# Display70_Cape.net
KiCad netlist of a schematic drawn in EAGLE
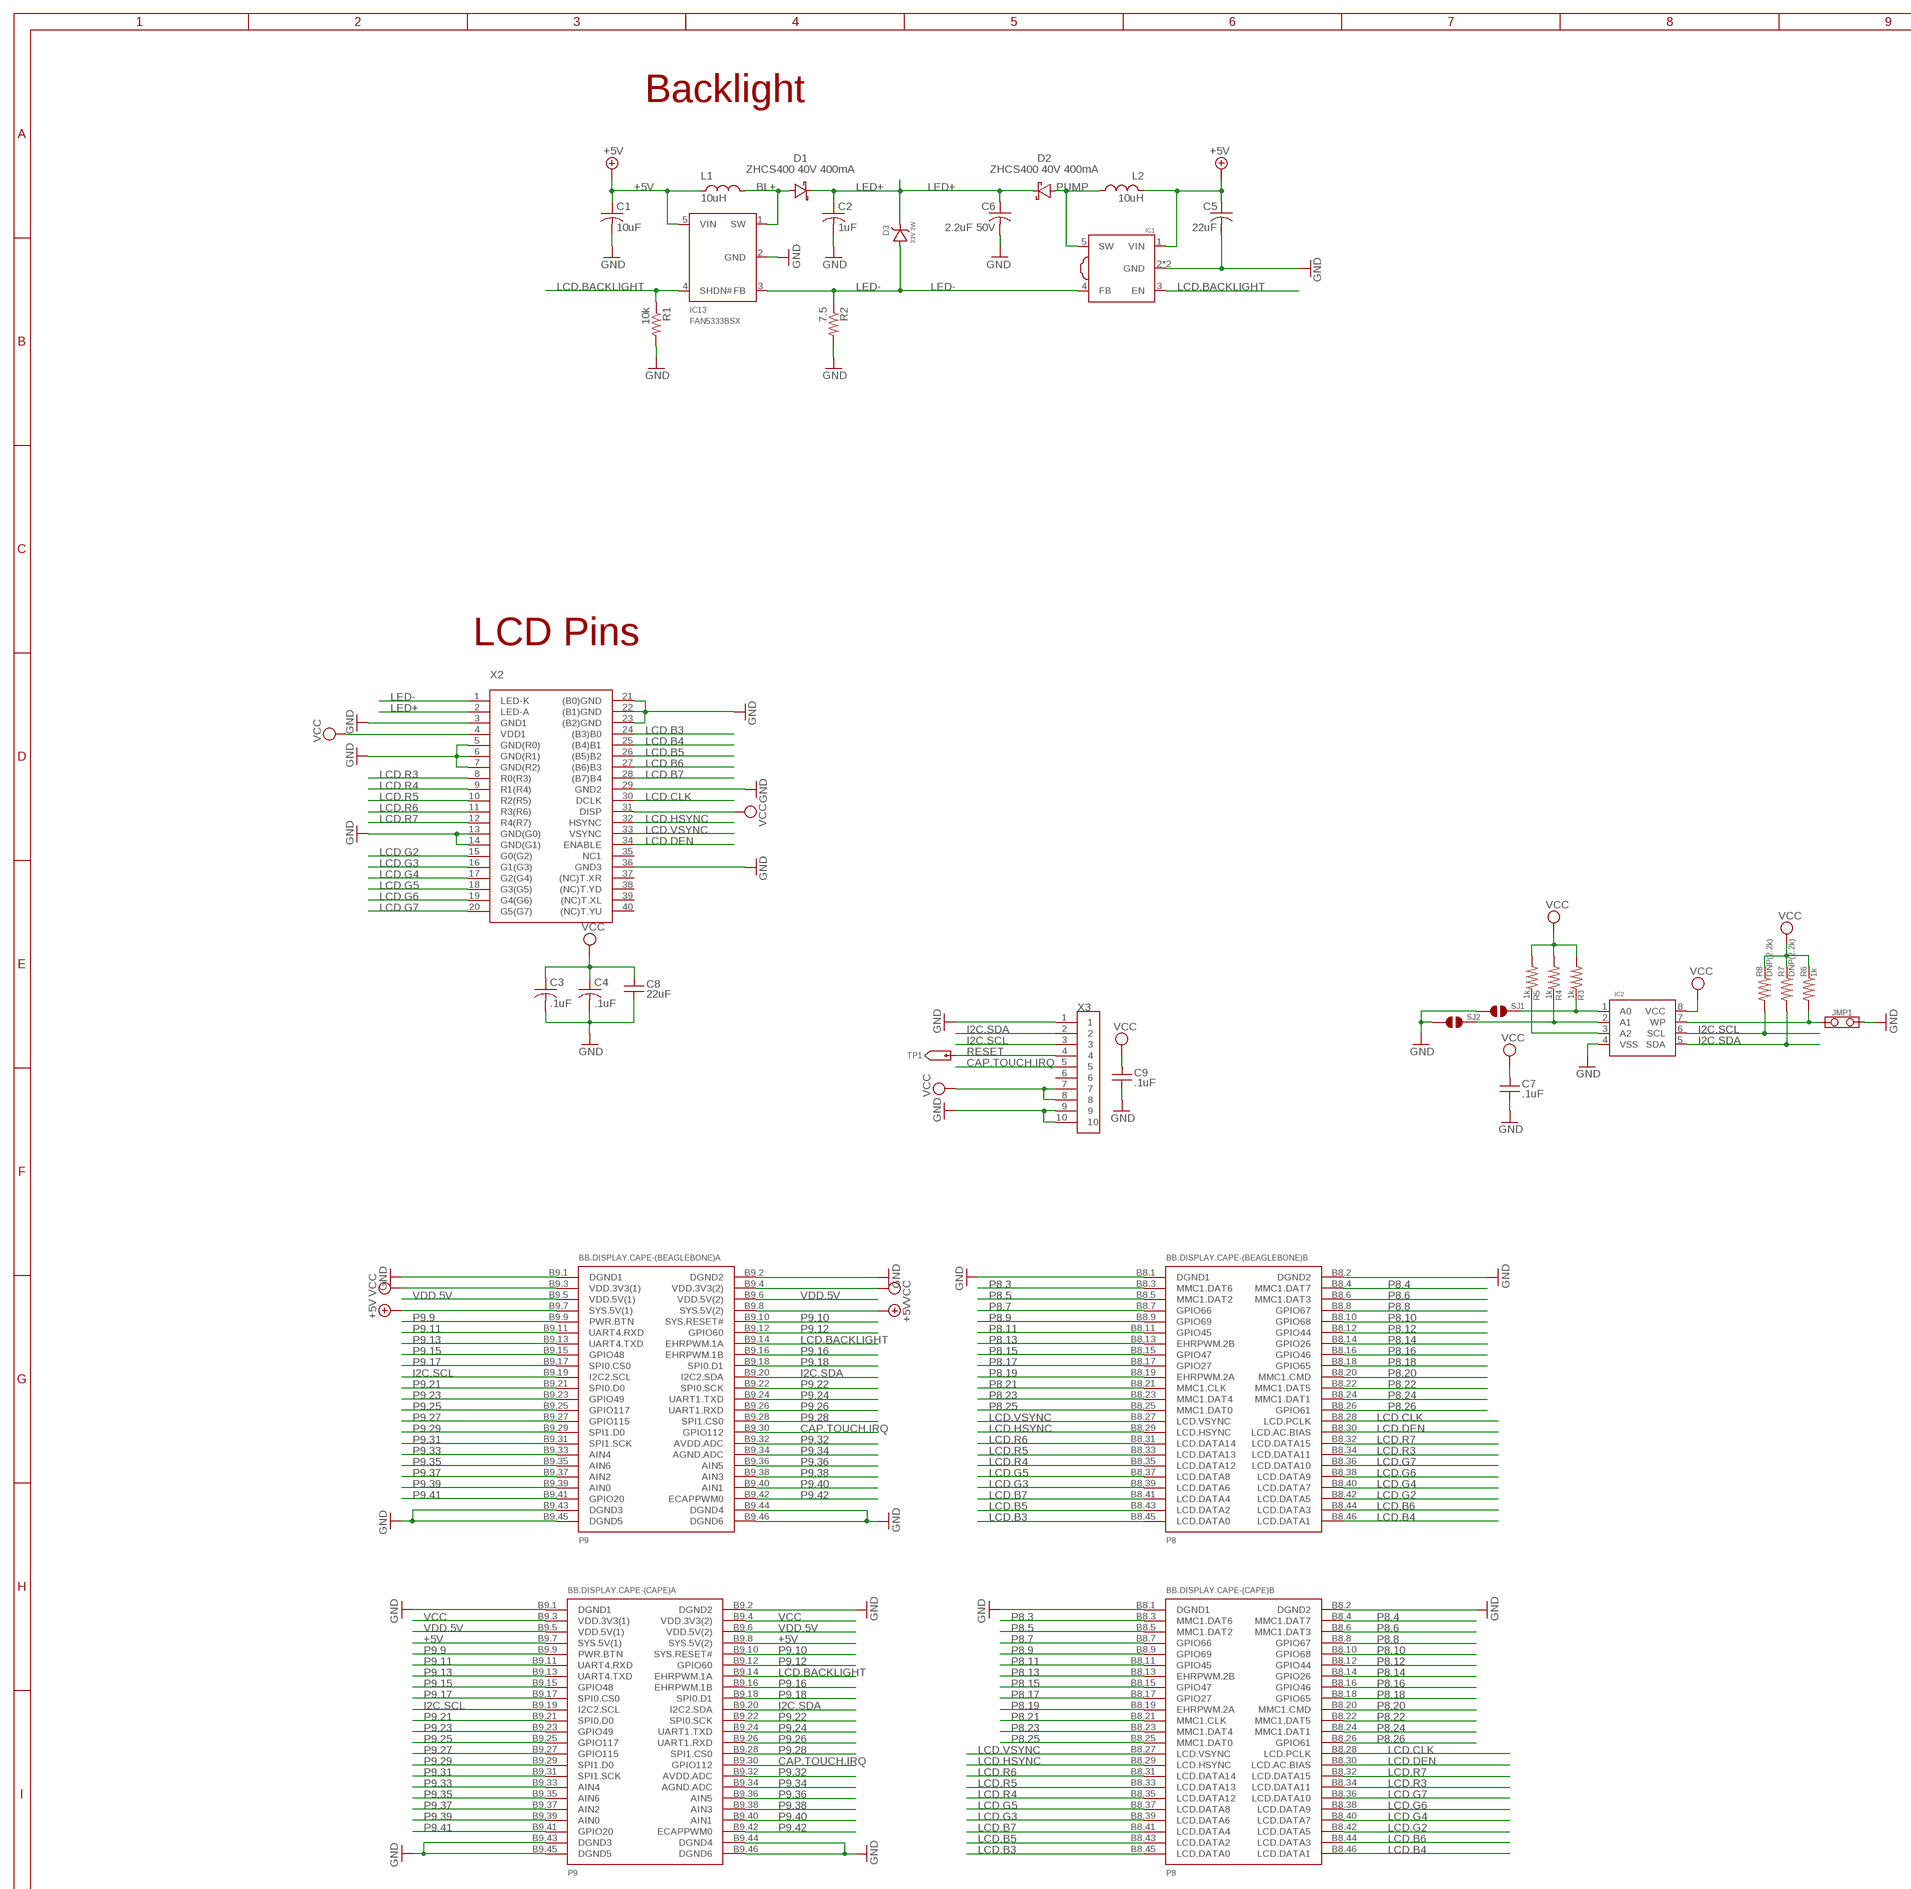
[diagram p0: schematic, sheet 1, part 1 of 2]
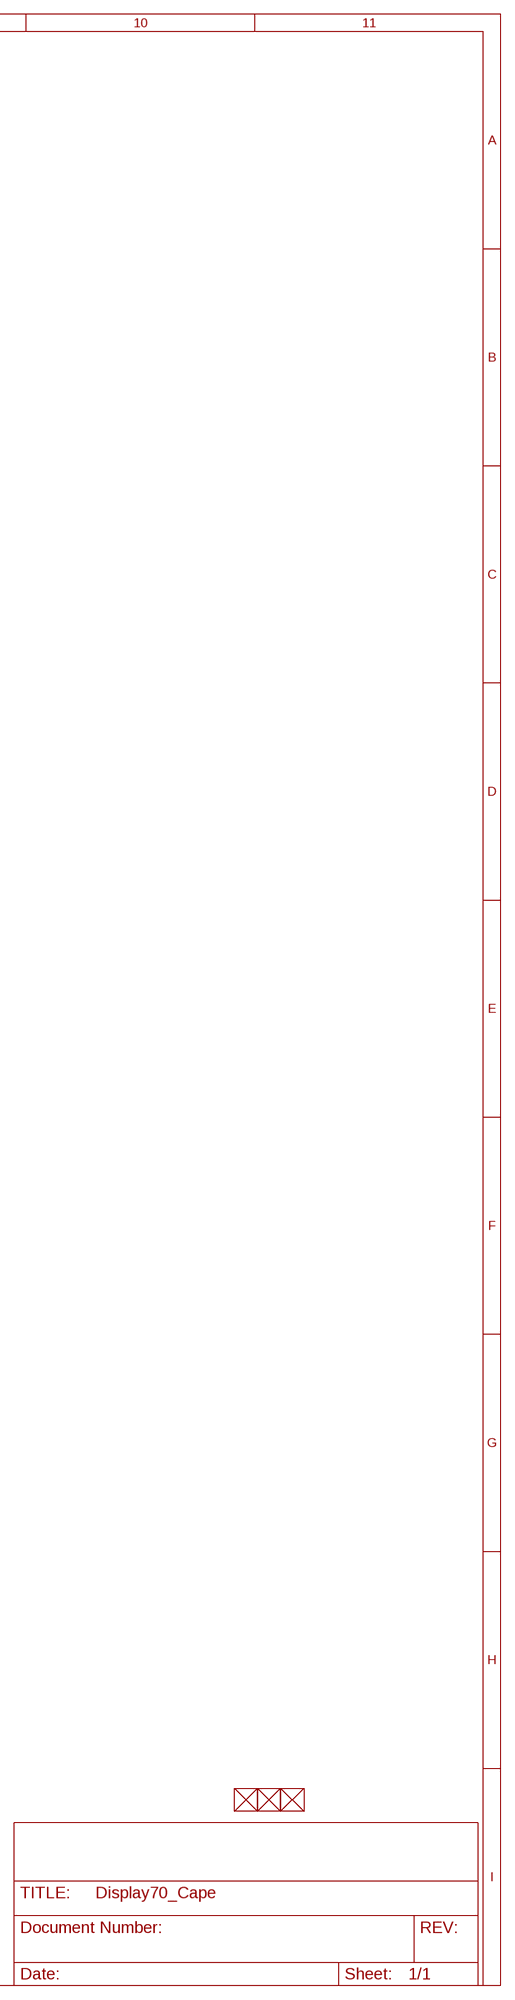
[diagram p1: schematic, sheet 1, part 2 of 2]

(export (version "E")
  (design (tool "Eeschema 10.0.6"))
  (components
    (comp (ref "BB.DISPLAY.CAPE-(BEAGLEBONE)")
      (value "BEAGLEBONE.CAPE.DISPLAY-7.BEAGLEBONE")
      (footprint "eagle-import:BEAGLEBONE.CAPE.DISPLAY-7.BEAGLEBONE")
      (libsource (lib "eagle-import") (part "BEAGLEBONE.CAPE.DISPLAY-7.BEAGLEBONE"))
    )
    (comp (ref "BB.DISPLAY.CAPE-(CAPE)")
      (value "BEAGLEBONE.CAPE.DISPLAY-7.CAPE")
      (footprint "eagle-import:BEAGLEBONE.CAPE.DISPLAY-7.CAPE")
      (libsource (lib "eagle-import") (part "BEAGLEBONE.CAPE.DISPLAY-7.CAPE"))
    )
    (comp (ref "C1")
      (value "10uF")
      (footprint "eagle-import:C0603K")
      (libsource (lib "eagle-import") (part "C-USC0603K"))
    )
    (comp (ref "C2")
      (value "1uF")
      (footprint "eagle-import:C0805K")
      (libsource (lib "eagle-import") (part "C-USC0805K"))
    )
    (comp (ref "C3")
      (value ".1uF")
      (footprint "eagle-import:C0402K")
      (libsource (lib "eagle-import") (part "C-USC0402K"))
    )
    (comp (ref "C4")
      (value ".1uF")
      (footprint "eagle-import:C0402K")
      (libsource (lib "eagle-import") (part "C-USC0402K"))
    )
    (comp (ref "C5")
      (value "22uF")
      (footprint "eagle-import:C0603K")
      (libsource (lib "eagle-import") (part "C-USC0603K"))
    )
    (comp (ref "C6")
      (value "2.2uF 50V")
      (footprint "eagle-import:C0805K")
      (libsource (lib "eagle-import") (part "C-USC0805K"))
    )
    (comp (ref "C7")
      (value ".1uF")
      (footprint "eagle-import:0402")
      (libsource (lib "eagle-import") (part "CAPACITOR-(INCH)-0402"))
    )
    (comp (ref "C8")
      (value "22uF")
      (footprint "eagle-import:0805")
      (libsource (lib "eagle-import") (part "CAPACITOR-(INCH)-0805"))
    )
    (comp (ref "C9")
      (value ".1uF")
      (footprint "eagle-import:0402")
      (libsource (lib "eagle-import") (part "CAPACITOR-(INCH)-0402"))
    )
    (comp (ref "D1")
      (value "ZHCS400 40V 400mA")
      (footprint "eagle-import:SOD323(NXP)WAVE")
      (libsource (lib "eagle-import") (part "DIODE-SCHOTTKY-(NXP)-SOD323-(WAVE)"))
    )
    (comp (ref "D2")
      (value "ZHCS400 40V 400mA")
      (footprint "eagle-import:SOD323(NXP)WAVE")
      (libsource (lib "eagle-import") (part "DIODE-SCHOTTKY-(NXP)-SOD323-(WAVE)"))
    )
    (comp (ref "D3")
      (value "33V 3W")
      (footprint "eagle-import:SMB(ON.SEMI)")
      (libsource (lib "eagle-import") (part "DIODE-ZENER-"))
    )
    (comp (ref "FUD1")
      (value "FIDUCIAL")
      (footprint "eagle-import:FIDUCIAL_40MIL")
      (libsource (lib "eagle-import") (part "FIDUCIAL"))
    )
    (comp (ref "FUD2")
      (value "FIDUCIAL")
      (footprint "eagle-import:FIDUCIAL_40MIL")
      (libsource (lib "eagle-import") (part "FIDUCIAL"))
    )
    (comp (ref "FUD3")
      (value "FIDUCIAL")
      (footprint "eagle-import:FIDUCIAL_40MIL")
      (libsource (lib "eagle-import") (part "FIDUCIAL"))
    )
    (comp (ref "IC1")
      (value "PT4110")
      (footprint "eagle-import:SOT89-5(DIODES)")
      (libsource (lib "eagle-import") (part "PT4110"))
    )
    (comp (ref "IC2")
      (value "CAT24C32")
      (footprint "eagle-import:UDFN8,2X3(ON-SEMI)")
      (libsource (lib "eagle-import") (part "CAT24C32"))
    )
    (comp (ref "IC13")
      (value "FAN5333BSX")
      (footprint "eagle-import:SOT23-5(FAIRCHILD)")
      (libsource (lib "eagle-import") (part "FAN533X"))
    )
    (comp (ref "JMP1")
      (value "JUMPER-(X2)")
      (footprint "eagle-import:JUMPER-(X2)")
      (libsource (lib "eagle-import") (part "JUMPER-(X2)"))
    )
    (comp (ref "L1")
      (value "10uH")
      (footprint "eagle-import:NRS(TAIYO.YUDEN)")
      (libsource (lib "eagle-import") (part "INDUCTOR-(TAIYO-YUDEN)-NRS5030"))
    )
    (comp (ref "L2")
      (value "10uH")
      (footprint "eagle-import:NRS(TAIYO.YUDEN)")
      (libsource (lib "eagle-import") (part "INDUCTOR-(TAIYO-YUDEN)-NRS5030"))
    )
    (comp (ref "R1")
      (value "10k")
      (footprint "eagle-import:R0603")
      (libsource (lib "eagle-import") (part "R-US_R0603"))
    )
    (comp (ref "R2")
      (value "7.5")
      (footprint "eagle-import:R0603")
      (libsource (lib "eagle-import") (part "R-US_R0603"))
    )
    (comp (ref "R3")
      (value "1k")
      (footprint "eagle-import:0402")
      (libsource (lib "eagle-import") (part "RESISTOR-(INCH)-0402"))
    )
    (comp (ref "R4")
      (value "1k")
      (footprint "eagle-import:0402")
      (libsource (lib "eagle-import") (part "RESISTOR-(INCH)-0402"))
    )
    (comp (ref "R5")
      (value "1k")
      (footprint "eagle-import:0402")
      (libsource (lib "eagle-import") (part "RESISTOR-(INCH)-0402"))
    )
    (comp (ref "R6")
      (value "1k")
      (footprint "eagle-import:0402")
      (libsource (lib "eagle-import") (part "RESISTOR-(INCH)-0402"))
    )
    (comp (ref "R7")
      (value "DNP(2.2k)")
      (footprint "eagle-import:0402")
      (libsource (lib "eagle-import") (part "RESISTOR-(INCH)-0402"))
    )
    (comp (ref "R8")
      (value "DNP(2.2k)")
      (footprint "eagle-import:0402")
      (libsource (lib "eagle-import") (part "RESISTOR-(INCH)-0402"))
    )
    (comp (ref "SJ1")
      (value "SOLDER.JOINT-(INCH)-0402")
      (footprint "eagle-import:SOLDER.JOINT(0402)")
      (libsource (lib "eagle-import") (part "SOLDER.JOINT-(INCH)-0402"))
    )
    (comp (ref "SJ2")
      (value "SOLDER.JOINT-(INCH)-0402")
      (footprint "eagle-import:SOLDER.JOINT(0402)")
      (libsource (lib "eagle-import") (part "SOLDER.JOINT-(INCH)-0402"))
    )
    (comp (ref "TP1")
      (value "TESTPAD/W_HOLE_1X1")
      (footprint "eagle-import:TESTPAD_W_HOLE_1X1")
      (libsource (lib "eagle-import") (part "TESTPAD/W_HOLE_1X1"))
    )
    (comp (ref "X2")
      (value "LCD-40PIN_FFC/FPC_0.5MM_PITCH")
      (footprint "eagle-import:KISD04-40_T1_E")
      (libsource (lib "eagle-import") (part "LCD-40PIN_FFC/FPC_0.5MM_PITCH"))
    )
    (comp (ref "X3")
      (value "10-PIN-(0.5MM-PITCH)-FPC-CONNECTOR")
      (footprint "eagle-import:10-PIN-(0.5MM-PITCH)-FPC-CONNECTOR")
      (libsource (lib "eagle-import") (part "10-PIN-(0.5MM-PITCH)-FPC-CONNECTOR"))
    )
  )
  (nets
    (net (code "1") (name "+5V") (class "Default")
      (node (ref "BB.DISPLAY.CAPE-(BEAGLEBONE)") (pin "B9.7") (pinfunction "SYS.5V(1)_B9.7") (pintype "bidirectional"))
      (node (ref "BB.DISPLAY.CAPE-(BEAGLEBONE)") (pin "B9.8") (pinfunction "SYS.5V(2)_B9.8") (pintype "bidirectional"))
      (node (ref "BB.DISPLAY.CAPE-(CAPE)") (pin "B9.7") (pinfunction "SYS.5V(1)_B9.7") (pintype "bidirectional"))
      (node (ref "BB.DISPLAY.CAPE-(CAPE)") (pin "B9.8") (pinfunction "SYS.5V(2)_B9.8") (pintype "bidirectional"))
      (node (ref "C1") (pin "1") (pinfunction "1_1") (pintype "passive"))
      (node (ref "C5") (pin "1") (pinfunction "1_1") (pintype "passive"))
      (node (ref "IC1") (pin "1") (pinfunction "VIN_1") (pintype "bidirectional"))
      (node (ref "IC13") (pin "5") (pinfunction "VIN_5") (pintype "bidirectional"))
      (node (ref "L1") (pin "1") (pinfunction "1_1") (pintype "bidirectional"))
      (node (ref "L2") (pin "1") (pinfunction "1_1") (pintype "bidirectional"))
    )
    (net (code "2") (name "/BL+") (class "Default")
      (node (ref "D1") (pin "A") (pinfunction "ANODE_A") (pintype "bidirectional"))
      (node (ref "IC13") (pin "1") (pinfunction "SW_1") (pintype "bidirectional"))
      (node (ref "L1") (pin "2") (pinfunction "2_2") (pintype "bidirectional"))
    )
    (net (code "3") (name "/CAP.TOUCH.IRQ") (class "Default")
      (node (ref "BB.DISPLAY.CAPE-(BEAGLEBONE)") (pin "B9.30") (pinfunction "GPIO112_B9.30") (pintype "bidirectional"))
      (node (ref "BB.DISPLAY.CAPE-(CAPE)") (pin "B9.30") (pinfunction "GPIO112_B9.30") (pintype "bidirectional"))
      (node (ref "X3") (pin "5") (pinfunction "5_5") (pintype "bidirectional"))
    )
    (net (code "4") (name "/I2C.SCL") (class "Default")
      (node (ref "BB.DISPLAY.CAPE-(BEAGLEBONE)") (pin "B9.19") (pinfunction "I2C2.SCL_B9.19") (pintype "bidirectional"))
      (node (ref "BB.DISPLAY.CAPE-(CAPE)") (pin "B9.19") (pinfunction "I2C2.SCL_B9.19") (pintype "bidirectional"))
      (node (ref "IC2") (pin "6") (pinfunction "SCL_6") (pintype "bidirectional"))
      (node (ref "R8") (pin "1") (pinfunction "1_1") (pintype "bidirectional"))
      (node (ref "X3") (pin "3") (pinfunction "3_3") (pintype "bidirectional"))
    )
    (net (code "5") (name "/I2C.SDA") (class "Default")
      (node (ref "BB.DISPLAY.CAPE-(BEAGLEBONE)") (pin "B9.20") (pinfunction "I2C2.SDA_B9.20") (pintype "bidirectional"))
      (node (ref "BB.DISPLAY.CAPE-(CAPE)") (pin "B9.20") (pinfunction "I2C2.SDA_B9.20") (pintype "bidirectional"))
      (node (ref "IC2") (pin "5") (pinfunction "SDA_5") (pintype "bidirectional"))
      (node (ref "R7") (pin "1") (pinfunction "1_1") (pintype "bidirectional"))
      (node (ref "X3") (pin "2") (pinfunction "2_2") (pintype "bidirectional"))
    )
    (net (code "6") (name "/LCD.B3") (class "Default")
      (node (ref "BB.DISPLAY.CAPE-(BEAGLEBONE)") (pin "B8.45") (pinfunction "LCD.DATA0_B8.45") (pintype "bidirectional"))
      (node (ref "BB.DISPLAY.CAPE-(CAPE)") (pin "B8.45") (pinfunction "LCD.DATA0_B8.45") (pintype "bidirectional"))
      (node (ref "X2") (pin "24") (pinfunction "(B3)B0_24") (pintype "bidirectional"))
    )
    (net (code "7") (name "/LCD.B4") (class "Default")
      (node (ref "BB.DISPLAY.CAPE-(BEAGLEBONE)") (pin "B8.46") (pinfunction "LCD.DATA1_B8.46") (pintype "bidirectional"))
      (node (ref "BB.DISPLAY.CAPE-(CAPE)") (pin "B8.46") (pinfunction "LCD.DATA1_B8.46") (pintype "bidirectional"))
      (node (ref "X2") (pin "25") (pinfunction "(B4)B1_25") (pintype "bidirectional"))
    )
    (net (code "8") (name "/LCD.B5") (class "Default")
      (node (ref "BB.DISPLAY.CAPE-(BEAGLEBONE)") (pin "B8.43") (pinfunction "LCD.DATA2_B8.43") (pintype "bidirectional"))
      (node (ref "BB.DISPLAY.CAPE-(CAPE)") (pin "B8.43") (pinfunction "LCD.DATA2_B8.43") (pintype "bidirectional"))
      (node (ref "X2") (pin "26") (pinfunction "(B5)B2_26") (pintype "bidirectional"))
    )
    (net (code "9") (name "/LCD.B6") (class "Default")
      (node (ref "BB.DISPLAY.CAPE-(BEAGLEBONE)") (pin "B8.44") (pinfunction "LCD.DATA3_B8.44") (pintype "bidirectional"))
      (node (ref "BB.DISPLAY.CAPE-(CAPE)") (pin "B8.44") (pinfunction "LCD.DATA3_B8.44") (pintype "bidirectional"))
      (node (ref "X2") (pin "27") (pinfunction "(B6)B3_27") (pintype "bidirectional"))
    )
    (net (code "10") (name "/LCD.B7") (class "Default")
      (node (ref "BB.DISPLAY.CAPE-(BEAGLEBONE)") (pin "B8.41") (pinfunction "LCD.DATA4_B8.41") (pintype "bidirectional"))
      (node (ref "BB.DISPLAY.CAPE-(CAPE)") (pin "B8.41") (pinfunction "LCD.DATA4_B8.41") (pintype "bidirectional"))
      (node (ref "X2") (pin "28") (pinfunction "(B7)B4_28") (pintype "bidirectional"))
    )
    (net (code "11") (name "/LCD.BACKLIGHT") (class "Default")
      (node (ref "BB.DISPLAY.CAPE-(BEAGLEBONE)") (pin "B9.14") (pinfunction "EHRPWM.1A_B9.14") (pintype "bidirectional"))
      (node (ref "BB.DISPLAY.CAPE-(CAPE)") (pin "B9.14") (pinfunction "EHRPWM.1A_B9.14") (pintype "bidirectional"))
      (node (ref "IC1") (pin "3") (pinfunction "EN_3") (pintype "bidirectional"))
      (node (ref "IC13") (pin "4") (pinfunction "SHDN#_4") (pintype "bidirectional"))
      (node (ref "R1") (pin "1") (pinfunction "1_1") (pintype "passive"))
    )
    (net (code "12") (name "/LCD.CLK") (class "Default")
      (node (ref "BB.DISPLAY.CAPE-(BEAGLEBONE)") (pin "B8.28") (pinfunction "LCD.PCLK_B8.28") (pintype "bidirectional"))
      (node (ref "BB.DISPLAY.CAPE-(CAPE)") (pin "B8.28") (pinfunction "LCD.PCLK_B8.28") (pintype "bidirectional"))
      (node (ref "X2") (pin "30") (pinfunction "DCLK_30") (pintype "bidirectional"))
    )
    (net (code "13") (name "/LCD.DEN") (class "Default")
      (node (ref "BB.DISPLAY.CAPE-(BEAGLEBONE)") (pin "B8.30") (pinfunction "LCD.AC.BIAS_B8.30") (pintype "bidirectional"))
      (node (ref "BB.DISPLAY.CAPE-(CAPE)") (pin "B8.30") (pinfunction "LCD.AC.BIAS_B8.30") (pintype "bidirectional"))
      (node (ref "X2") (pin "34") (pinfunction "ENABLE_34") (pintype "bidirectional"))
    )
    (net (code "14") (name "/LCD.G2") (class "Default")
      (node (ref "BB.DISPLAY.CAPE-(BEAGLEBONE)") (pin "B8.42") (pinfunction "LCD.DATA5_B8.42") (pintype "bidirectional"))
      (node (ref "BB.DISPLAY.CAPE-(CAPE)") (pin "B8.42") (pinfunction "LCD.DATA5_B8.42") (pintype "bidirectional"))
      (node (ref "X2") (pin "15") (pinfunction "G0(G2)_15") (pintype "bidirectional"))
    )
    (net (code "15") (name "/LCD.G3") (class "Default")
      (node (ref "BB.DISPLAY.CAPE-(BEAGLEBONE)") (pin "B8.39") (pinfunction "LCD.DATA6_B8.39") (pintype "bidirectional"))
      (node (ref "BB.DISPLAY.CAPE-(CAPE)") (pin "B8.39") (pinfunction "LCD.DATA6_B8.39") (pintype "bidirectional"))
      (node (ref "X2") (pin "16") (pinfunction "G1(G3)_16") (pintype "bidirectional"))
    )
    (net (code "16") (name "/LCD.G4") (class "Default")
      (node (ref "BB.DISPLAY.CAPE-(BEAGLEBONE)") (pin "B8.40") (pinfunction "LCD.DATA7_B8.40") (pintype "bidirectional"))
      (node (ref "BB.DISPLAY.CAPE-(CAPE)") (pin "B8.40") (pinfunction "LCD.DATA7_B8.40") (pintype "bidirectional"))
      (node (ref "X2") (pin "17") (pinfunction "G2(G4)_17") (pintype "bidirectional"))
    )
    (net (code "17") (name "/LCD.G5") (class "Default")
      (node (ref "BB.DISPLAY.CAPE-(BEAGLEBONE)") (pin "B8.37") (pinfunction "LCD.DATA8_B8.37") (pintype "bidirectional"))
      (node (ref "BB.DISPLAY.CAPE-(CAPE)") (pin "B8.37") (pinfunction "LCD.DATA8_B8.37") (pintype "bidirectional"))
      (node (ref "X2") (pin "18") (pinfunction "G3(G5)_18") (pintype "bidirectional"))
    )
    (net (code "18") (name "/LCD.G6") (class "Default")
      (node (ref "BB.DISPLAY.CAPE-(BEAGLEBONE)") (pin "B8.38") (pinfunction "LCD.DATA9_B8.38") (pintype "bidirectional"))
      (node (ref "BB.DISPLAY.CAPE-(CAPE)") (pin "B8.38") (pinfunction "LCD.DATA9_B8.38") (pintype "bidirectional"))
      (node (ref "X2") (pin "19") (pinfunction "G4(G6)_19") (pintype "bidirectional"))
    )
    (net (code "19") (name "/LCD.G7") (class "Default")
      (node (ref "BB.DISPLAY.CAPE-(BEAGLEBONE)") (pin "B8.36") (pinfunction "LCD.DATA10_B8.36") (pintype "bidirectional"))
      (node (ref "BB.DISPLAY.CAPE-(CAPE)") (pin "B8.36") (pinfunction "LCD.DATA10_B8.36") (pintype "bidirectional"))
      (node (ref "X2") (pin "20") (pinfunction "G5(G7)_20") (pintype "bidirectional"))
    )
    (net (code "20") (name "/LCD.HSYNC") (class "Default")
      (node (ref "BB.DISPLAY.CAPE-(BEAGLEBONE)") (pin "B8.29") (pinfunction "LCD.HSYNC_B8.29") (pintype "bidirectional"))
      (node (ref "BB.DISPLAY.CAPE-(CAPE)") (pin "B8.29") (pinfunction "LCD.HSYNC_B8.29") (pintype "bidirectional"))
      (node (ref "X2") (pin "32") (pinfunction "HSYNC_32") (pintype "bidirectional"))
    )
    (net (code "21") (name "/LCD.R3") (class "Default")
      (node (ref "BB.DISPLAY.CAPE-(BEAGLEBONE)") (pin "B8.34") (pinfunction "LCD.DATA11_B8.34") (pintype "bidirectional"))
      (node (ref "BB.DISPLAY.CAPE-(CAPE)") (pin "B8.34") (pinfunction "LCD.DATA11_B8.34") (pintype "bidirectional"))
      (node (ref "X2") (pin "8") (pinfunction "R0(R3)_8") (pintype "bidirectional"))
    )
    (net (code "22") (name "/LCD.R4") (class "Default")
      (node (ref "BB.DISPLAY.CAPE-(BEAGLEBONE)") (pin "B8.35") (pinfunction "LCD.DATA12_B8.35") (pintype "bidirectional"))
      (node (ref "BB.DISPLAY.CAPE-(CAPE)") (pin "B8.35") (pinfunction "LCD.DATA12_B8.35") (pintype "bidirectional"))
      (node (ref "X2") (pin "9") (pinfunction "R1(R4)_9") (pintype "bidirectional"))
    )
    (net (code "23") (name "/LCD.R5") (class "Default")
      (node (ref "BB.DISPLAY.CAPE-(BEAGLEBONE)") (pin "B8.33") (pinfunction "LCD.DATA13_B8.33") (pintype "bidirectional"))
      (node (ref "BB.DISPLAY.CAPE-(CAPE)") (pin "B8.33") (pinfunction "LCD.DATA13_B8.33") (pintype "bidirectional"))
      (node (ref "X2") (pin "10") (pinfunction "R2(R5)_10") (pintype "bidirectional"))
    )
    (net (code "24") (name "/LCD.R6") (class "Default")
      (node (ref "BB.DISPLAY.CAPE-(BEAGLEBONE)") (pin "B8.31") (pinfunction "LCD.DATA14_B8.31") (pintype "bidirectional"))
      (node (ref "BB.DISPLAY.CAPE-(CAPE)") (pin "B8.31") (pinfunction "LCD.DATA14_B8.31") (pintype "bidirectional"))
      (node (ref "X2") (pin "11") (pinfunction "R3(R6)_11") (pintype "bidirectional"))
    )
    (net (code "25") (name "/LCD.R7") (class "Default")
      (node (ref "BB.DISPLAY.CAPE-(BEAGLEBONE)") (pin "B8.32") (pinfunction "LCD.DATA15_B8.32") (pintype "bidirectional"))
      (node (ref "BB.DISPLAY.CAPE-(CAPE)") (pin "B8.32") (pinfunction "LCD.DATA15_B8.32") (pintype "bidirectional"))
      (node (ref "X2") (pin "12") (pinfunction "R4(R7)_12") (pintype "bidirectional"))
    )
    (net (code "26") (name "/LCD.VSYNC") (class "Default")
      (node (ref "BB.DISPLAY.CAPE-(BEAGLEBONE)") (pin "B8.27") (pinfunction "LCD.VSYNC_B8.27") (pintype "bidirectional"))
      (node (ref "BB.DISPLAY.CAPE-(CAPE)") (pin "B8.27") (pinfunction "LCD.VSYNC_B8.27") (pintype "bidirectional"))
      (node (ref "X2") (pin "33") (pinfunction "VSYNC_33") (pintype "bidirectional"))
    )
    (net (code "27") (name "/LED+") (class "Default")
      (node (ref "C2") (pin "1") (pinfunction "1_1") (pintype "passive"))
      (node (ref "C6") (pin "1") (pinfunction "1_1") (pintype "passive"))
      (node (ref "D1") (pin "C") (pinfunction "CATHODE_C") (pintype "bidirectional"))
      (node (ref "D2") (pin "C") (pinfunction "CATHODE_C") (pintype "bidirectional"))
      (node (ref "D3") (pin "K") (pinfunction "K_K") (pintype "bidirectional"))
      (node (ref "X2") (pin "2") (pinfunction "LED-A_2") (pintype "bidirectional"))
    )
    (net (code "28") (name "/LED-") (class "Default")
      (node (ref "D3") (pin "A") (pinfunction "A_A") (pintype "bidirectional"))
      (node (ref "IC1") (pin "4") (pinfunction "FB_4") (pintype "bidirectional"))
      (node (ref "IC13") (pin "3") (pinfunction "FB_3") (pintype "bidirectional"))
      (node (ref "R2") (pin "1") (pinfunction "1_1") (pintype "passive"))
      (node (ref "X2") (pin "1") (pinfunction "LED-K_1") (pintype "bidirectional"))
    )
    (net (code "29") (name "/P8.3") (class "Default")
      (node (ref "BB.DISPLAY.CAPE-(BEAGLEBONE)") (pin "B8.3") (pinfunction "MMC1.DAT6_B8.3") (pintype "bidirectional"))
      (node (ref "BB.DISPLAY.CAPE-(CAPE)") (pin "B8.3") (pinfunction "MMC1.DAT6_B8.3") (pintype "bidirectional"))
    )
    (net (code "30") (name "/P8.4") (class "Default")
      (node (ref "BB.DISPLAY.CAPE-(BEAGLEBONE)") (pin "B8.4") (pinfunction "MMC1.DAT7_B8.4") (pintype "bidirectional"))
      (node (ref "BB.DISPLAY.CAPE-(CAPE)") (pin "B8.4") (pinfunction "MMC1.DAT7_B8.4") (pintype "bidirectional"))
    )
    (net (code "31") (name "/P8.5") (class "Default")
      (node (ref "BB.DISPLAY.CAPE-(BEAGLEBONE)") (pin "B8.5") (pinfunction "MMC1.DAT2_B8.5") (pintype "bidirectional"))
      (node (ref "BB.DISPLAY.CAPE-(CAPE)") (pin "B8.5") (pinfunction "MMC1.DAT2_B8.5") (pintype "bidirectional"))
    )
    (net (code "32") (name "/P8.6") (class "Default")
      (node (ref "BB.DISPLAY.CAPE-(BEAGLEBONE)") (pin "B8.6") (pinfunction "MMC1.DAT3_B8.6") (pintype "bidirectional"))
      (node (ref "BB.DISPLAY.CAPE-(CAPE)") (pin "B8.6") (pinfunction "MMC1.DAT3_B8.6") (pintype "bidirectional"))
    )
    (net (code "33") (name "/P8.7") (class "Default")
      (node (ref "BB.DISPLAY.CAPE-(BEAGLEBONE)") (pin "B8.7") (pinfunction "GPIO66_B8.7") (pintype "bidirectional"))
      (node (ref "BB.DISPLAY.CAPE-(CAPE)") (pin "B8.7") (pinfunction "GPIO66_B8.7") (pintype "bidirectional"))
    )
    (net (code "34") (name "/P8.8") (class "Default")
      (node (ref "BB.DISPLAY.CAPE-(BEAGLEBONE)") (pin "B8.8") (pinfunction "GPIO67_B8.8") (pintype "bidirectional"))
      (node (ref "BB.DISPLAY.CAPE-(CAPE)") (pin "B8.8") (pinfunction "GPIO67_B8.8") (pintype "bidirectional"))
    )
    (net (code "35") (name "/P8.9") (class "Default")
      (node (ref "BB.DISPLAY.CAPE-(BEAGLEBONE)") (pin "B8.9") (pinfunction "GPIO69_B8.9") (pintype "bidirectional"))
      (node (ref "BB.DISPLAY.CAPE-(CAPE)") (pin "B8.9") (pinfunction "GPIO69_B8.9") (pintype "bidirectional"))
    )
    (net (code "36") (name "/P8.10") (class "Default")
      (node (ref "BB.DISPLAY.CAPE-(BEAGLEBONE)") (pin "B8.10") (pinfunction "GPIO68_B8.10") (pintype "bidirectional"))
      (node (ref "BB.DISPLAY.CAPE-(CAPE)") (pin "B8.10") (pinfunction "GPIO68_B8.10") (pintype "bidirectional"))
    )
    (net (code "37") (name "/P8.11") (class "Default")
      (node (ref "BB.DISPLAY.CAPE-(BEAGLEBONE)") (pin "B8.11") (pinfunction "GPIO45_B8.11") (pintype "bidirectional"))
      (node (ref "BB.DISPLAY.CAPE-(CAPE)") (pin "B8.11") (pinfunction "GPIO45_B8.11") (pintype "bidirectional"))
    )
    (net (code "38") (name "/P8.12") (class "Default")
      (node (ref "BB.DISPLAY.CAPE-(BEAGLEBONE)") (pin "B8.12") (pinfunction "GPIO44_B8.12") (pintype "bidirectional"))
      (node (ref "BB.DISPLAY.CAPE-(CAPE)") (pin "B8.12") (pinfunction "GPIO44_B8.12") (pintype "bidirectional"))
    )
    (net (code "39") (name "/P8.13") (class "Default")
      (node (ref "BB.DISPLAY.CAPE-(BEAGLEBONE)") (pin "B8.13") (pinfunction "EHRPWM.2B_B8.13") (pintype "bidirectional"))
      (node (ref "BB.DISPLAY.CAPE-(CAPE)") (pin "B8.13") (pinfunction "EHRPWM.2B_B8.13") (pintype "bidirectional"))
    )
    (net (code "40") (name "/P8.14") (class "Default")
      (node (ref "BB.DISPLAY.CAPE-(BEAGLEBONE)") (pin "B8.14") (pinfunction "GPIO26_B8.14") (pintype "bidirectional"))
      (node (ref "BB.DISPLAY.CAPE-(CAPE)") (pin "B8.14") (pinfunction "GPIO26_B8.14") (pintype "bidirectional"))
    )
    (net (code "41") (name "/P8.15") (class "Default")
      (node (ref "BB.DISPLAY.CAPE-(BEAGLEBONE)") (pin "B8.15") (pinfunction "GPIO47_B8.15") (pintype "bidirectional"))
      (node (ref "BB.DISPLAY.CAPE-(CAPE)") (pin "B8.15") (pinfunction "GPIO47_B8.15") (pintype "bidirectional"))
    )
    (net (code "42") (name "/P8.16") (class "Default")
      (node (ref "BB.DISPLAY.CAPE-(BEAGLEBONE)") (pin "B8.16") (pinfunction "GPIO46_B8.16") (pintype "bidirectional"))
      (node (ref "BB.DISPLAY.CAPE-(CAPE)") (pin "B8.16") (pinfunction "GPIO46_B8.16") (pintype "bidirectional"))
    )
    (net (code "43") (name "/P8.17") (class "Default")
      (node (ref "BB.DISPLAY.CAPE-(BEAGLEBONE)") (pin "B8.17") (pinfunction "GPIO27_B8.17") (pintype "bidirectional"))
      (node (ref "BB.DISPLAY.CAPE-(CAPE)") (pin "B8.17") (pinfunction "GPIO27_B8.17") (pintype "bidirectional"))
    )
    (net (code "44") (name "/P8.18") (class "Default")
      (node (ref "BB.DISPLAY.CAPE-(BEAGLEBONE)") (pin "B8.18") (pinfunction "GPIO65_B8.18") (pintype "bidirectional"))
      (node (ref "BB.DISPLAY.CAPE-(CAPE)") (pin "B8.18") (pinfunction "GPIO65_B8.18") (pintype "bidirectional"))
    )
    (net (code "45") (name "/P8.19") (class "Default")
      (node (ref "BB.DISPLAY.CAPE-(BEAGLEBONE)") (pin "B8.19") (pinfunction "EHRPWM.2A_B8.19") (pintype "bidirectional"))
      (node (ref "BB.DISPLAY.CAPE-(CAPE)") (pin "B8.19") (pinfunction "EHRPWM.2A_B8.19") (pintype "bidirectional"))
    )
    (net (code "46") (name "/P8.20") (class "Default")
      (node (ref "BB.DISPLAY.CAPE-(BEAGLEBONE)") (pin "B8.20") (pinfunction "MMC1.CMD_B8.20") (pintype "bidirectional"))
      (node (ref "BB.DISPLAY.CAPE-(CAPE)") (pin "B8.20") (pinfunction "MMC1.CMD_B8.20") (pintype "bidirectional"))
    )
    (net (code "47") (name "/P8.21") (class "Default")
      (node (ref "BB.DISPLAY.CAPE-(BEAGLEBONE)") (pin "B8.21") (pinfunction "MMC1.CLK_B8.21") (pintype "bidirectional"))
      (node (ref "BB.DISPLAY.CAPE-(CAPE)") (pin "B8.21") (pinfunction "MMC1.CLK_B8.21") (pintype "bidirectional"))
    )
    (net (code "48") (name "/P8.22") (class "Default")
      (node (ref "BB.DISPLAY.CAPE-(BEAGLEBONE)") (pin "B8.22") (pinfunction "MMC1.DAT5_B8.22") (pintype "bidirectional"))
      (node (ref "BB.DISPLAY.CAPE-(CAPE)") (pin "B8.22") (pinfunction "MMC1.DAT5_B8.22") (pintype "bidirectional"))
    )
    (net (code "49") (name "/P8.23") (class "Default")
      (node (ref "BB.DISPLAY.CAPE-(BEAGLEBONE)") (pin "B8.23") (pinfunction "MMC1.DAT4_B8.23") (pintype "bidirectional"))
      (node (ref "BB.DISPLAY.CAPE-(CAPE)") (pin "B8.23") (pinfunction "MMC1.DAT4_B8.23") (pintype "bidirectional"))
    )
    (net (code "50") (name "/P8.24") (class "Default")
      (node (ref "BB.DISPLAY.CAPE-(BEAGLEBONE)") (pin "B8.24") (pinfunction "MMC1.DAT1_B8.24") (pintype "bidirectional"))
      (node (ref "BB.DISPLAY.CAPE-(CAPE)") (pin "B8.24") (pinfunction "MMC1.DAT1_B8.24") (pintype "bidirectional"))
    )
    (net (code "51") (name "/P8.25") (class "Default")
      (node (ref "BB.DISPLAY.CAPE-(BEAGLEBONE)") (pin "B8.25") (pinfunction "MMC1.DAT0_B8.25") (pintype "bidirectional"))
      (node (ref "BB.DISPLAY.CAPE-(CAPE)") (pin "B8.25") (pinfunction "MMC1.DAT0_B8.25") (pintype "bidirectional"))
    )
    (net (code "52") (name "/P8.26") (class "Default")
      (node (ref "BB.DISPLAY.CAPE-(BEAGLEBONE)") (pin "B8.26") (pinfunction "GPIO61_B8.26") (pintype "bidirectional"))
      (node (ref "BB.DISPLAY.CAPE-(CAPE)") (pin "B8.26") (pinfunction "GPIO61_B8.26") (pintype "bidirectional"))
    )
    (net (code "53") (name "/P9.9") (class "Default")
      (node (ref "BB.DISPLAY.CAPE-(BEAGLEBONE)") (pin "B9.9") (pinfunction "PWR.BTN_B9.9") (pintype "bidirectional"))
      (node (ref "BB.DISPLAY.CAPE-(CAPE)") (pin "B9.9") (pinfunction "PWR.BTN_B9.9") (pintype "bidirectional"))
    )
    (net (code "54") (name "/P9.10") (class "Default")
      (node (ref "BB.DISPLAY.CAPE-(BEAGLEBONE)") (pin "B9.10") (pinfunction "SYS.RESET#_B9.10") (pintype "bidirectional"))
      (node (ref "BB.DISPLAY.CAPE-(CAPE)") (pin "B9.10") (pinfunction "SYS.RESET#_B9.10") (pintype "bidirectional"))
    )
    (net (code "55") (name "/P9.11") (class "Default")
      (node (ref "BB.DISPLAY.CAPE-(BEAGLEBONE)") (pin "B9.11") (pinfunction "UART4.RXD_B9.11") (pintype "bidirectional"))
      (node (ref "BB.DISPLAY.CAPE-(CAPE)") (pin "B9.11") (pinfunction "UART4.RXD_B9.11") (pintype "bidirectional"))
    )
    (net (code "56") (name "/P9.12") (class "Default")
      (node (ref "BB.DISPLAY.CAPE-(BEAGLEBONE)") (pin "B9.12") (pinfunction "GPIO60_B9.12") (pintype "bidirectional"))
      (node (ref "BB.DISPLAY.CAPE-(CAPE)") (pin "B9.12") (pinfunction "GPIO60_B9.12") (pintype "bidirectional"))
    )
    (net (code "57") (name "/P9.13") (class "Default")
      (node (ref "BB.DISPLAY.CAPE-(BEAGLEBONE)") (pin "B9.13") (pinfunction "UART4.TXD_B9.13") (pintype "bidirectional"))
      (node (ref "BB.DISPLAY.CAPE-(CAPE)") (pin "B9.13") (pinfunction "UART4.TXD_B9.13") (pintype "bidirectional"))
    )
    (net (code "58") (name "/P9.15") (class "Default")
      (node (ref "BB.DISPLAY.CAPE-(BEAGLEBONE)") (pin "B9.15") (pinfunction "GPIO48_B9.15") (pintype "bidirectional"))
      (node (ref "BB.DISPLAY.CAPE-(CAPE)") (pin "B9.15") (pinfunction "GPIO48_B9.15") (pintype "bidirectional"))
    )
    (net (code "59") (name "/P9.16") (class "Default")
      (node (ref "BB.DISPLAY.CAPE-(BEAGLEBONE)") (pin "B9.16") (pinfunction "EHRPWM.1B_B9.16") (pintype "bidirectional"))
      (node (ref "BB.DISPLAY.CAPE-(CAPE)") (pin "B9.16") (pinfunction "EHRPWM.1B_B9.16") (pintype "bidirectional"))
    )
    (net (code "60") (name "/P9.17") (class "Default")
      (node (ref "BB.DISPLAY.CAPE-(BEAGLEBONE)") (pin "B9.17") (pinfunction "SPI0.CS0_B9.17") (pintype "bidirectional"))
      (node (ref "BB.DISPLAY.CAPE-(CAPE)") (pin "B9.17") (pinfunction "SPI0.CS0_B9.17") (pintype "bidirectional"))
    )
    (net (code "61") (name "/P9.18") (class "Default")
      (node (ref "BB.DISPLAY.CAPE-(BEAGLEBONE)") (pin "B9.18") (pinfunction "SPI0.D1_B9.18") (pintype "bidirectional"))
      (node (ref "BB.DISPLAY.CAPE-(CAPE)") (pin "B9.18") (pinfunction "SPI0.D1_B9.18") (pintype "bidirectional"))
    )
    (net (code "62") (name "/P9.21") (class "Default")
      (node (ref "BB.DISPLAY.CAPE-(BEAGLEBONE)") (pin "B9.21") (pinfunction "SPI0.D0_B9.21") (pintype "bidirectional"))
      (node (ref "BB.DISPLAY.CAPE-(CAPE)") (pin "B9.21") (pinfunction "SPI0.D0_B9.21") (pintype "bidirectional"))
    )
    (net (code "63") (name "/P9.22") (class "Default")
      (node (ref "BB.DISPLAY.CAPE-(BEAGLEBONE)") (pin "B9.22") (pinfunction "SPI0.SCK_B9.22") (pintype "bidirectional"))
      (node (ref "BB.DISPLAY.CAPE-(CAPE)") (pin "B9.22") (pinfunction "SPI0.SCK_B9.22") (pintype "bidirectional"))
    )
    (net (code "64") (name "/P9.23") (class "Default")
      (node (ref "BB.DISPLAY.CAPE-(BEAGLEBONE)") (pin "B9.23") (pinfunction "GPIO49_B9.23") (pintype "bidirectional"))
      (node (ref "BB.DISPLAY.CAPE-(CAPE)") (pin "B9.23") (pinfunction "GPIO49_B9.23") (pintype "bidirectional"))
    )
    (net (code "65") (name "/P9.24") (class "Default")
      (node (ref "BB.DISPLAY.CAPE-(BEAGLEBONE)") (pin "B9.24") (pinfunction "UART1.TXD_B9.24") (pintype "bidirectional"))
      (node (ref "BB.DISPLAY.CAPE-(CAPE)") (pin "B9.24") (pinfunction "UART1.TXD_B9.24") (pintype "bidirectional"))
    )
    (net (code "66") (name "/P9.25") (class "Default")
      (node (ref "BB.DISPLAY.CAPE-(BEAGLEBONE)") (pin "B9.25") (pinfunction "GPIO117_B9.25") (pintype "bidirectional"))
      (node (ref "BB.DISPLAY.CAPE-(CAPE)") (pin "B9.25") (pinfunction "GPIO117_B9.25") (pintype "bidirectional"))
    )
    (net (code "67") (name "/P9.26") (class "Default")
      (node (ref "BB.DISPLAY.CAPE-(BEAGLEBONE)") (pin "B9.26") (pinfunction "UART1.RXD_B9.26") (pintype "bidirectional"))
      (node (ref "BB.DISPLAY.CAPE-(CAPE)") (pin "B9.26") (pinfunction "UART1.RXD_B9.26") (pintype "bidirectional"))
    )
    (net (code "68") (name "/P9.27") (class "Default")
      (node (ref "BB.DISPLAY.CAPE-(BEAGLEBONE)") (pin "B9.27") (pinfunction "GPIO115_B9.27") (pintype "bidirectional"))
      (node (ref "BB.DISPLAY.CAPE-(CAPE)") (pin "B9.27") (pinfunction "GPIO115_B9.27") (pintype "bidirectional"))
    )
    (net (code "69") (name "/P9.28") (class "Default")
      (node (ref "BB.DISPLAY.CAPE-(BEAGLEBONE)") (pin "B9.28") (pinfunction "SPI1.CS0_B9.28") (pintype "bidirectional"))
      (node (ref "BB.DISPLAY.CAPE-(CAPE)") (pin "B9.28") (pinfunction "SPI1.CS0_B9.28") (pintype "bidirectional"))
    )
    (net (code "70") (name "/P9.29") (class "Default")
      (node (ref "BB.DISPLAY.CAPE-(BEAGLEBONE)") (pin "B9.29") (pinfunction "SPI1.D0_B9.29") (pintype "bidirectional"))
      (node (ref "BB.DISPLAY.CAPE-(CAPE)") (pin "B9.29") (pinfunction "SPI1.D0_B9.29") (pintype "bidirectional"))
    )
    (net (code "71") (name "/P9.31") (class "Default")
      (node (ref "BB.DISPLAY.CAPE-(BEAGLEBONE)") (pin "B9.31") (pinfunction "SPI1.SCK_B9.31") (pintype "bidirectional"))
      (node (ref "BB.DISPLAY.CAPE-(CAPE)") (pin "B9.31") (pinfunction "SPI1.SCK_B9.31") (pintype "bidirectional"))
    )
    (net (code "72") (name "/P9.32") (class "Default")
      (node (ref "BB.DISPLAY.CAPE-(BEAGLEBONE)") (pin "B9.32") (pinfunction "AVDD.ADC_B9.32") (pintype "bidirectional"))
      (node (ref "BB.DISPLAY.CAPE-(CAPE)") (pin "B9.32") (pinfunction "AVDD.ADC_B9.32") (pintype "bidirectional"))
    )
    (net (code "73") (name "/P9.33") (class "Default")
      (node (ref "BB.DISPLAY.CAPE-(BEAGLEBONE)") (pin "B9.33") (pinfunction "AIN4_B9.33") (pintype "bidirectional"))
      (node (ref "BB.DISPLAY.CAPE-(CAPE)") (pin "B9.33") (pinfunction "AIN4_B9.33") (pintype "bidirectional"))
    )
    (net (code "74") (name "/P9.34") (class "Default")
      (node (ref "BB.DISPLAY.CAPE-(BEAGLEBONE)") (pin "B9.34") (pinfunction "AGND.ADC_B9.34") (pintype "bidirectional"))
      (node (ref "BB.DISPLAY.CAPE-(CAPE)") (pin "B9.34") (pinfunction "AGND.ADC_B9.34") (pintype "bidirectional"))
    )
    (net (code "75") (name "/P9.35") (class "Default")
      (node (ref "BB.DISPLAY.CAPE-(BEAGLEBONE)") (pin "B9.35") (pinfunction "AIN6_B9.35") (pintype "bidirectional"))
      (node (ref "BB.DISPLAY.CAPE-(CAPE)") (pin "B9.35") (pinfunction "AIN6_B9.35") (pintype "bidirectional"))
    )
    (net (code "76") (name "/P9.36") (class "Default")
      (node (ref "BB.DISPLAY.CAPE-(BEAGLEBONE)") (pin "B9.36") (pinfunction "AIN5_B9.36") (pintype "bidirectional"))
      (node (ref "BB.DISPLAY.CAPE-(CAPE)") (pin "B9.36") (pinfunction "AIN5_B9.36") (pintype "bidirectional"))
    )
    (net (code "77") (name "/P9.37") (class "Default")
      (node (ref "BB.DISPLAY.CAPE-(BEAGLEBONE)") (pin "B9.37") (pinfunction "AIN2_B9.37") (pintype "bidirectional"))
      (node (ref "BB.DISPLAY.CAPE-(CAPE)") (pin "B9.37") (pinfunction "AIN2_B9.37") (pintype "bidirectional"))
    )
    (net (code "78") (name "/P9.38") (class "Default")
      (node (ref "BB.DISPLAY.CAPE-(BEAGLEBONE)") (pin "B9.38") (pinfunction "AIN3_B9.38") (pintype "bidirectional"))
      (node (ref "BB.DISPLAY.CAPE-(CAPE)") (pin "B9.38") (pinfunction "AIN3_B9.38") (pintype "bidirectional"))
    )
    (net (code "79") (name "/P9.39") (class "Default")
      (node (ref "BB.DISPLAY.CAPE-(BEAGLEBONE)") (pin "B9.39") (pinfunction "AIN0_B9.39") (pintype "bidirectional"))
      (node (ref "BB.DISPLAY.CAPE-(CAPE)") (pin "B9.39") (pinfunction "AIN0_B9.39") (pintype "bidirectional"))
    )
    (net (code "80") (name "/P9.40") (class "Default")
      (node (ref "BB.DISPLAY.CAPE-(BEAGLEBONE)") (pin "B9.40") (pinfunction "AIN1_B9.40") (pintype "bidirectional"))
      (node (ref "BB.DISPLAY.CAPE-(CAPE)") (pin "B9.40") (pinfunction "AIN1_B9.40") (pintype "bidirectional"))
    )
    (net (code "81") (name "/P9.41") (class "Default")
      (node (ref "BB.DISPLAY.CAPE-(BEAGLEBONE)") (pin "B9.41") (pinfunction "GPIO20_B9.41") (pintype "bidirectional"))
      (node (ref "BB.DISPLAY.CAPE-(CAPE)") (pin "B9.41") (pinfunction "GPIO20_B9.41") (pintype "bidirectional"))
    )
    (net (code "82") (name "/P9.42") (class "Default")
      (node (ref "BB.DISPLAY.CAPE-(BEAGLEBONE)") (pin "B9.42") (pinfunction "ECAPPWM0_B9.42") (pintype "bidirectional"))
      (node (ref "BB.DISPLAY.CAPE-(CAPE)") (pin "B9.42") (pinfunction "ECAPPWM0_B9.42") (pintype "bidirectional"))
    )
    (net (code "83") (name "/PUMP") (class "Default")
      (node (ref "D2") (pin "A") (pinfunction "ANODE_A") (pintype "bidirectional"))
      (node (ref "IC1") (pin "5") (pinfunction "SW_5") (pintype "bidirectional"))
      (node (ref "L2") (pin "2") (pinfunction "2_2") (pintype "bidirectional"))
    )
    (net (code "84") (name "/RESET") (class "Default")
      (node (ref "TP1") (pin "P$1") (pinfunction "TP_P$1") (pintype "bidirectional"))
      (node (ref "X3") (pin "4") (pinfunction "4_4") (pintype "bidirectional"))
    )
    (net (code "85") (name "/VDD.5V") (class "Default")
      (node (ref "BB.DISPLAY.CAPE-(BEAGLEBONE)") (pin "B9.5") (pinfunction "VDD.5V(1)_B9.5") (pintype "bidirectional"))
      (node (ref "BB.DISPLAY.CAPE-(BEAGLEBONE)") (pin "B9.6") (pinfunction "VDD.5V(2)_B9.6") (pintype "bidirectional"))
      (node (ref "BB.DISPLAY.CAPE-(CAPE)") (pin "B9.5") (pinfunction "VDD.5V(1)_B9.5") (pintype "bidirectional"))
      (node (ref "BB.DISPLAY.CAPE-(CAPE)") (pin "B9.6") (pinfunction "VDD.5V(2)_B9.6") (pintype "bidirectional"))
    )
    (net (code "86") (name "GND") (class "Default")
      (node (ref "BB.DISPLAY.CAPE-(BEAGLEBONE)") (pin "B8.1") (pinfunction "DGND1_B8.1") (pintype "bidirectional"))
      (node (ref "BB.DISPLAY.CAPE-(BEAGLEBONE)") (pin "B8.2") (pinfunction "DGND2_B8.2") (pintype "bidirectional"))
      (node (ref "BB.DISPLAY.CAPE-(BEAGLEBONE)") (pin "B9.1") (pinfunction "DGND1_B9.1") (pintype "bidirectional"))
      (node (ref "BB.DISPLAY.CAPE-(BEAGLEBONE)") (pin "B9.2") (pinfunction "DGND2_B9.2") (pintype "bidirectional"))
      (node (ref "BB.DISPLAY.CAPE-(BEAGLEBONE)") (pin "B9.43") (pinfunction "DGND3_B9.43") (pintype "bidirectional"))
      (node (ref "BB.DISPLAY.CAPE-(BEAGLEBONE)") (pin "B9.44") (pinfunction "DGND4_B9.44") (pintype "bidirectional"))
      (node (ref "BB.DISPLAY.CAPE-(BEAGLEBONE)") (pin "B9.45") (pinfunction "DGND5_B9.45") (pintype "bidirectional"))
      (node (ref "BB.DISPLAY.CAPE-(BEAGLEBONE)") (pin "B9.46") (pinfunction "DGND6_B9.46") (pintype "bidirectional"))
      (node (ref "BB.DISPLAY.CAPE-(CAPE)") (pin "B8.1") (pinfunction "DGND1_B8.1") (pintype "bidirectional"))
      (node (ref "BB.DISPLAY.CAPE-(CAPE)") (pin "B8.2") (pinfunction "DGND2_B8.2") (pintype "bidirectional"))
      (node (ref "BB.DISPLAY.CAPE-(CAPE)") (pin "B9.1") (pinfunction "DGND1_B9.1") (pintype "bidirectional"))
      (node (ref "BB.DISPLAY.CAPE-(CAPE)") (pin "B9.2") (pinfunction "DGND2_B9.2") (pintype "bidirectional"))
      (node (ref "BB.DISPLAY.CAPE-(CAPE)") (pin "B9.43") (pinfunction "DGND3_B9.43") (pintype "bidirectional"))
      (node (ref "BB.DISPLAY.CAPE-(CAPE)") (pin "B9.44") (pinfunction "DGND4_B9.44") (pintype "bidirectional"))
      (node (ref "BB.DISPLAY.CAPE-(CAPE)") (pin "B9.45") (pinfunction "DGND5_B9.45") (pintype "bidirectional"))
      (node (ref "BB.DISPLAY.CAPE-(CAPE)") (pin "B9.46") (pinfunction "DGND6_B9.46") (pintype "bidirectional"))
      (node (ref "C1") (pin "2") (pinfunction "2_2") (pintype "passive"))
      (node (ref "C2") (pin "2") (pinfunction "2_2") (pintype "passive"))
      (node (ref "C3") (pin "2") (pinfunction "2_2") (pintype "passive"))
      (node (ref "C4") (pin "2") (pinfunction "2_2") (pintype "passive"))
      (node (ref "C5") (pin "2") (pinfunction "2_2") (pintype "passive"))
      (node (ref "C6") (pin "2") (pinfunction "2_2") (pintype "passive"))
      (node (ref "C7") (pin "2") (pinfunction "2_2") (pintype "bidirectional"))
      (node (ref "C8") (pin "2") (pinfunction "2_2") (pintype "bidirectional"))
      (node (ref "C9") (pin "2") (pinfunction "2_2") (pintype "bidirectional"))
      (node (ref "IC1") (pin "2") (pinfunction "GND_2") (pintype "bidirectional"))
      (node (ref "IC1") (pin "THERMAL") (pinfunction "GND_THERMAL") (pintype "bidirectional"))
      (node (ref "IC13") (pin "2") (pinfunction "GND_2") (pintype "bidirectional"))
      (node (ref "IC2") (pin "4") (pinfunction "VSS_4") (pintype "bidirectional"))
      (node (ref "JMP1") (pin "2") (pinfunction "2_2") (pintype "bidirectional"))
      (node (ref "R1") (pin "2") (pinfunction "2_2") (pintype "passive"))
      (node (ref "R2") (pin "2") (pinfunction "2_2") (pintype "passive"))
      (node (ref "SJ1") (pin "1") (pinfunction "1_1") (pintype "bidirectional"))
      (node (ref "SJ2") (pin "1") (pinfunction "1_1") (pintype "bidirectional"))
      (node (ref "X2") (pin "13") (pinfunction "GND(G0)_13") (pintype "bidirectional"))
      (node (ref "X2") (pin "14") (pinfunction "GND(G1)_14") (pintype "bidirectional"))
      (node (ref "X2") (pin "21") (pinfunction "(B0)GND_21") (pintype "bidirectional"))
      (node (ref "X2") (pin "22") (pinfunction "(B1)GND_22") (pintype "bidirectional"))
      (node (ref "X2") (pin "23") (pinfunction "(B2)GND_23") (pintype "bidirectional"))
      (node (ref "X2") (pin "29") (pinfunction "GND2_29") (pintype "bidirectional"))
      (node (ref "X2") (pin "3") (pinfunction "GND1_3") (pintype "bidirectional"))
      (node (ref "X2") (pin "36") (pinfunction "GND3_36") (pintype "bidirectional"))
      (node (ref "X2") (pin "5") (pinfunction "GND(R0)_5") (pintype "bidirectional"))
      (node (ref "X2") (pin "6") (pinfunction "GND(R1)_6") (pintype "bidirectional"))
      (node (ref "X2") (pin "7") (pinfunction "GND(R2)_7") (pintype "bidirectional"))
      (node (ref "X3") (pin "1") (pinfunction "1_1") (pintype "bidirectional"))
      (node (ref "X3") (pin "10") (pinfunction "10_10") (pintype "bidirectional"))
      (node (ref "X3") (pin "9") (pinfunction "9_9") (pintype "bidirectional"))
    )
    (net (code "87") (name "Net-(IC2-A0)") (class "Default")
      (node (ref "IC2") (pin "1") (pinfunction "A0_1") (pintype "bidirectional"))
      (node (ref "R3") (pin "2") (pinfunction "2_2") (pintype "bidirectional"))
      (node (ref "SJ1") (pin "2") (pinfunction "2_2") (pintype "bidirectional"))
    )
    (net (code "88") (name "Net-(IC2-A1)") (class "Default")
      (node (ref "IC2") (pin "2") (pinfunction "A1_2") (pintype "bidirectional"))
      (node (ref "R4") (pin "2") (pinfunction "2_2") (pintype "bidirectional"))
      (node (ref "SJ2") (pin "2") (pinfunction "2_2") (pintype "bidirectional"))
    )
    (net (code "89") (name "Net-(IC2-A2)") (class "Default")
      (node (ref "IC2") (pin "3") (pinfunction "A2_3") (pintype "bidirectional"))
      (node (ref "R5") (pin "2") (pinfunction "2_2") (pintype "bidirectional"))
    )
    (net (code "90") (name "Net-(IC2-WP)") (class "Default")
      (node (ref "IC2") (pin "7") (pinfunction "WP_7") (pintype "bidirectional"))
      (node (ref "JMP1") (pin "1") (pinfunction "1_1") (pintype "bidirectional"))
      (node (ref "R6") (pin "1") (pinfunction "1_1") (pintype "bidirectional"))
    )
    (net (code "91") (name "VCC") (class "Default")
      (node (ref "BB.DISPLAY.CAPE-(BEAGLEBONE)") (pin "B9.3") (pinfunction "VDD.3V3(1)_B9.3") (pintype "bidirectional"))
      (node (ref "BB.DISPLAY.CAPE-(BEAGLEBONE)") (pin "B9.4") (pinfunction "VDD.3V3(2)_B9.4") (pintype "bidirectional"))
      (node (ref "BB.DISPLAY.CAPE-(CAPE)") (pin "B9.3") (pinfunction "VDD.3V3(1)_B9.3") (pintype "bidirectional"))
      (node (ref "BB.DISPLAY.CAPE-(CAPE)") (pin "B9.4") (pinfunction "VDD.3V3(2)_B9.4") (pintype "bidirectional"))
      (node (ref "C3") (pin "1") (pinfunction "1_1") (pintype "passive"))
      (node (ref "C4") (pin "1") (pinfunction "1_1") (pintype "passive"))
      (node (ref "C7") (pin "1") (pinfunction "1_1") (pintype "bidirectional"))
      (node (ref "C8") (pin "1") (pinfunction "1_1") (pintype "bidirectional"))
      (node (ref "C9") (pin "1") (pinfunction "1_1") (pintype "bidirectional"))
      (node (ref "IC2") (pin "8") (pinfunction "VCC_8") (pintype "bidirectional"))
      (node (ref "R3") (pin "1") (pinfunction "1_1") (pintype "bidirectional"))
      (node (ref "R4") (pin "1") (pinfunction "1_1") (pintype "bidirectional"))
      (node (ref "R5") (pin "1") (pinfunction "1_1") (pintype "bidirectional"))
      (node (ref "R6") (pin "2") (pinfunction "2_2") (pintype "bidirectional"))
      (node (ref "R7") (pin "2") (pinfunction "2_2") (pintype "bidirectional"))
      (node (ref "R8") (pin "2") (pinfunction "2_2") (pintype "bidirectional"))
      (node (ref "X2") (pin "31") (pinfunction "DISP_31") (pintype "bidirectional"))
      (node (ref "X2") (pin "4") (pinfunction "VDD1_4") (pintype "bidirectional"))
      (node (ref "X3") (pin "7") (pinfunction "7_7") (pintype "bidirectional"))
      (node (ref "X3") (pin "8") (pinfunction "8_8") (pintype "bidirectional"))
    )
    (net (code "92") (name "unconnected-(FUD1-PadP$1)") (class "Default")
      (node (ref "FUD1") (pin "P$1") (pinfunction "P$1_P$1") (pintype "no_connect"))
    )
    (net (code "93") (name "unconnected-(FUD2-PadP$1)") (class "Default")
      (node (ref "FUD2") (pin "P$1") (pinfunction "P$1_P$1") (pintype "no_connect"))
    )
    (net (code "94") (name "unconnected-(FUD3-PadP$1)") (class "Default")
      (node (ref "FUD3") (pin "P$1") (pinfunction "P$1_P$1") (pintype "no_connect"))
    )
    (net (code "95") (name "unconnected-(X2-(NC)T.XL-Pad39)") (class "Default")
      (node (ref "X2") (pin "39") (pinfunction "(NC)T.XL_39") (pintype "bidirectional"))
    )
    (net (code "96") (name "unconnected-(X2-(NC)T.XR-Pad37)") (class "Default")
      (node (ref "X2") (pin "37") (pinfunction "(NC)T.XR_37") (pintype "bidirectional"))
    )
    (net (code "97") (name "unconnected-(X2-(NC)T.YD-Pad38)") (class "Default")
      (node (ref "X2") (pin "38") (pinfunction "(NC)T.YD_38") (pintype "bidirectional"))
    )
    (net (code "98") (name "unconnected-(X2-(NC)T.YU-Pad40)") (class "Default")
      (node (ref "X2") (pin "40") (pinfunction "(NC)T.YU_40") (pintype "bidirectional"))
    )
    (net (code "99") (name "unconnected-(X2-NC1-Pad35)") (class "Default")
      (node (ref "X2") (pin "35") (pinfunction "NC1_35") (pintype "bidirectional"))
    )
    (net (code "100") (name "unconnected-(X3-Pad6)") (class "Default")
      (node (ref "X3") (pin "6") (pinfunction "6_6") (pintype "bidirectional"))
    )
  )
)
